# Quick_Mix.net
KiCad netlist of a schematic drawn in EAGLE
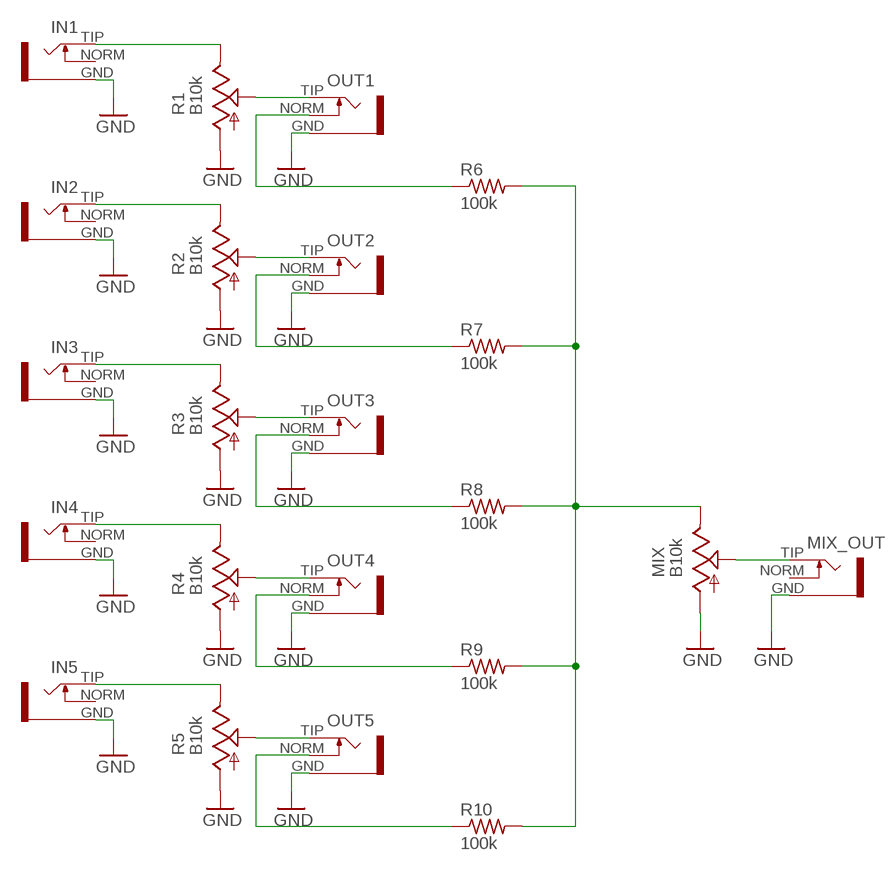
[diagram p0: schematic, sheet 1]

(export (version "E")
  (design (tool "Eeschema 10.0.6"))
  (components
    (comp (ref "IN1")
      (value "INSTRUO_S_JACK_SMALL2")
      (footprint "eagle-import:INSTRUO_S_JACK_SMALL2")
      (libsource (lib "eagle-import") (part "INSTRUO_S_JACK_SMALL2"))
    )
    (comp (ref "IN2")
      (value "INSTRUO_S_JACK_SMALL2")
      (footprint "eagle-import:INSTRUO_S_JACK_SMALL2")
      (libsource (lib "eagle-import") (part "INSTRUO_S_JACK_SMALL2"))
    )
    (comp (ref "IN3")
      (value "INSTRUO_S_JACK_SMALL2")
      (footprint "eagle-import:INSTRUO_S_JACK_SMALL2")
      (libsource (lib "eagle-import") (part "INSTRUO_S_JACK_SMALL2"))
    )
    (comp (ref "IN4")
      (value "INSTRUO_S_JACK_SMALL2")
      (footprint "eagle-import:INSTRUO_S_JACK_SMALL2")
      (libsource (lib "eagle-import") (part "INSTRUO_S_JACK_SMALL2"))
    )
    (comp (ref "IN5")
      (value "INSTRUO_S_JACK_SMALL2")
      (footprint "eagle-import:INSTRUO_S_JACK_SMALL2")
      (libsource (lib "eagle-import") (part "INSTRUO_S_JACK_SMALL2"))
    )
    (comp (ref "MIX")
      (value "B10k")
      (footprint "eagle-import:OG-POTS_ALPS_POT_VERTICAL")
      (libsource (lib "eagle-import") (part "OG-POTS_POT_USVERTICAL"))
    )
    (comp (ref "MIX_OUT")
      (value "INSTRUO_S_JACK_SMALL2")
      (footprint "eagle-import:INSTRUO_S_JACK_SMALL2")
      (libsource (lib "eagle-import") (part "INSTRUO_S_JACK_SMALL2"))
    )
    (comp (ref "OUT1")
      (value "INSTRUO_S_JACK_S2_INV")
      (footprint "eagle-import:INSTRUO_S_JACK_S2_INV")
      (libsource (lib "eagle-import") (part "INSTRUO_S_JACK_S2_INV"))
    )
    (comp (ref "OUT2")
      (value "INSTRUO_S_JACK_S2_INV")
      (footprint "eagle-import:INSTRUO_S_JACK_S2_INV")
      (libsource (lib "eagle-import") (part "INSTRUO_S_JACK_S2_INV"))
    )
    (comp (ref "OUT3")
      (value "INSTRUO_S_JACK_S2_INV")
      (footprint "eagle-import:INSTRUO_S_JACK_S2_INV")
      (libsource (lib "eagle-import") (part "INSTRUO_S_JACK_S2_INV"))
    )
    (comp (ref "OUT4")
      (value "INSTRUO_S_JACK_S2_INV")
      (footprint "eagle-import:INSTRUO_S_JACK_S2_INV")
      (libsource (lib "eagle-import") (part "INSTRUO_S_JACK_S2_INV"))
    )
    (comp (ref "OUT5")
      (value "INSTRUO_S_JACK_S2_INV")
      (footprint "eagle-import:INSTRUO_S_JACK_S2_INV")
      (libsource (lib "eagle-import") (part "INSTRUO_S_JACK_S2_INV"))
    )
    (comp (ref "R1")
      (value "B10k")
      (footprint "eagle-import:OG-POTS_ALPS_POT_VERTICAL")
      (libsource (lib "eagle-import") (part "OG-POTS_POT_USVERTICAL"))
    )
    (comp (ref "R2")
      (value "B10k")
      (footprint "eagle-import:OG-POTS_ALPS_POT_VERTICAL")
      (libsource (lib "eagle-import") (part "OG-POTS_POT_USVERTICAL"))
    )
    (comp (ref "R3")
      (value "B10k")
      (footprint "eagle-import:OG-POTS_ALPS_POT_VERTICAL")
      (libsource (lib "eagle-import") (part "OG-POTS_POT_USVERTICAL"))
    )
    (comp (ref "R4")
      (value "B10k")
      (footprint "eagle-import:OG-POTS_ALPS_POT_VERTICAL")
      (libsource (lib "eagle-import") (part "OG-POTS_POT_USVERTICAL"))
    )
    (comp (ref "R5")
      (value "B10k")
      (footprint "eagle-import:OG-POTS_ALPS_POT_VERTICAL")
      (libsource (lib "eagle-import") (part "OG-POTS_POT_USVERTICAL"))
    )
    (comp (ref "R6")
      (value "100k")
      (footprint "eagle-import:R0603")
      (libsource (lib "eagle-import") (part "R-US_R0603"))
    )
    (comp (ref "R7")
      (value "100k")
      (footprint "eagle-import:R0603")
      (libsource (lib "eagle-import") (part "R-US_R0603"))
    )
    (comp (ref "R8")
      (value "100k")
      (footprint "eagle-import:R0603")
      (libsource (lib "eagle-import") (part "R-US_R0603"))
    )
    (comp (ref "R9")
      (value "100k")
      (footprint "eagle-import:R0603")
      (libsource (lib "eagle-import") (part "R-US_R0603"))
    )
    (comp (ref "R10")
      (value "100k")
      (footprint "eagle-import:R0603")
      (libsource (lib "eagle-import") (part "R-US_R0603"))
    )
  )
  (nets
    (net (code "1") (name "GND") (class "Default")
      (node (ref "IN1") (pin "GND") (pinfunction "GND_GND") (pintype "passive"))
      (node (ref "IN2") (pin "GND") (pinfunction "GND_GND") (pintype "passive"))
      (node (ref "IN3") (pin "GND") (pinfunction "GND_GND") (pintype "passive"))
      (node (ref "IN4") (pin "GND") (pinfunction "GND_GND") (pintype "passive"))
      (node (ref "IN5") (pin "GND") (pinfunction "GND_GND") (pintype "passive"))
      (node (ref "MIX") (pin "P$3") (pinfunction "A_P$3") (pintype "passive"))
      (node (ref "MIX_OUT") (pin "GND") (pinfunction "GND_GND") (pintype "passive"))
      (node (ref "OUT1") (pin "GND") (pinfunction "GND_GND") (pintype "passive"))
      (node (ref "OUT2") (pin "GND") (pinfunction "GND_GND") (pintype "passive"))
      (node (ref "OUT3") (pin "GND") (pinfunction "GND_GND") (pintype "passive"))
      (node (ref "OUT4") (pin "GND") (pinfunction "GND_GND") (pintype "passive"))
      (node (ref "OUT5") (pin "GND") (pinfunction "GND_GND") (pintype "passive"))
      (node (ref "R1") (pin "P$3") (pinfunction "A_P$3") (pintype "passive"))
      (node (ref "R2") (pin "P$3") (pinfunction "A_P$3") (pintype "passive"))
      (node (ref "R3") (pin "P$3") (pinfunction "A_P$3") (pintype "passive"))
      (node (ref "R4") (pin "P$3") (pinfunction "A_P$3") (pintype "passive"))
      (node (ref "R5") (pin "P$3") (pinfunction "A_P$3") (pintype "passive"))
    )
    (net (code "2") (name "Net-(MIX-E)") (class "Default")
      (node (ref "MIX") (pin "P$1") (pinfunction "E_P$1") (pintype "passive"))
      (node (ref "R10") (pin "2") (pinfunction "2_2") (pintype "passive"))
      (node (ref "R6") (pin "2") (pinfunction "2_2") (pintype "passive"))
      (node (ref "R7") (pin "2") (pinfunction "2_2") (pintype "passive"))
      (node (ref "R8") (pin "2") (pinfunction "2_2") (pintype "passive"))
      (node (ref "R9") (pin "2") (pinfunction "2_2") (pintype "passive"))
    )
    (net (code "3") (name "Net-(MIX-S)") (class "Default")
      (node (ref "MIX") (pin "P$2") (pinfunction "S_P$2") (pintype "passive"))
      (node (ref "MIX_OUT") (pin "TIP") (pinfunction "TIP_TIP") (pintype "passive"))
    )
    (net (code "4") (name "Net-(OUT1-PadNORM)") (class "Default")
      (node (ref "OUT1") (pin "NORM") (pinfunction "NORM_NORM") (pintype "passive"))
      (node (ref "R6") (pin "1") (pinfunction "1_1") (pintype "passive"))
    )
    (net (code "5") (name "Net-(OUT2-PadNORM)") (class "Default")
      (node (ref "OUT2") (pin "NORM") (pinfunction "NORM_NORM") (pintype "passive"))
      (node (ref "R7") (pin "1") (pinfunction "1_1") (pintype "passive"))
    )
    (net (code "6") (name "Net-(OUT3-PadNORM)") (class "Default")
      (node (ref "OUT3") (pin "NORM") (pinfunction "NORM_NORM") (pintype "passive"))
      (node (ref "R8") (pin "1") (pinfunction "1_1") (pintype "passive"))
    )
    (net (code "7") (name "Net-(OUT4-PadNORM)") (class "Default")
      (node (ref "OUT4") (pin "NORM") (pinfunction "NORM_NORM") (pintype "passive"))
      (node (ref "R9") (pin "1") (pinfunction "1_1") (pintype "passive"))
    )
    (net (code "8") (name "Net-(OUT5-PadNORM)") (class "Default")
      (node (ref "OUT5") (pin "NORM") (pinfunction "NORM_NORM") (pintype "passive"))
      (node (ref "R10") (pin "1") (pinfunction "1_1") (pintype "passive"))
    )
    (net (code "9") (name "Net-(R1-E)") (class "Default")
      (node (ref "IN1") (pin "TIP") (pinfunction "TIP_TIP") (pintype "passive"))
      (node (ref "R1") (pin "P$1") (pinfunction "E_P$1") (pintype "passive"))
    )
    (net (code "10") (name "Net-(R1-S)") (class "Default")
      (node (ref "OUT1") (pin "TIP") (pinfunction "TIP_TIP") (pintype "passive"))
      (node (ref "R1") (pin "P$2") (pinfunction "S_P$2") (pintype "passive"))
    )
    (net (code "11") (name "Net-(R2-E)") (class "Default")
      (node (ref "IN2") (pin "TIP") (pinfunction "TIP_TIP") (pintype "passive"))
      (node (ref "R2") (pin "P$1") (pinfunction "E_P$1") (pintype "passive"))
    )
    (net (code "12") (name "Net-(R2-S)") (class "Default")
      (node (ref "OUT2") (pin "TIP") (pinfunction "TIP_TIP") (pintype "passive"))
      (node (ref "R2") (pin "P$2") (pinfunction "S_P$2") (pintype "passive"))
    )
    (net (code "13") (name "Net-(R3-E)") (class "Default")
      (node (ref "IN3") (pin "TIP") (pinfunction "TIP_TIP") (pintype "passive"))
      (node (ref "R3") (pin "P$1") (pinfunction "E_P$1") (pintype "passive"))
    )
    (net (code "14") (name "Net-(R3-S)") (class "Default")
      (node (ref "OUT3") (pin "TIP") (pinfunction "TIP_TIP") (pintype "passive"))
      (node (ref "R3") (pin "P$2") (pinfunction "S_P$2") (pintype "passive"))
    )
    (net (code "15") (name "Net-(R4-E)") (class "Default")
      (node (ref "IN4") (pin "TIP") (pinfunction "TIP_TIP") (pintype "passive"))
      (node (ref "R4") (pin "P$1") (pinfunction "E_P$1") (pintype "passive"))
    )
    (net (code "16") (name "Net-(R4-S)") (class "Default")
      (node (ref "OUT4") (pin "TIP") (pinfunction "TIP_TIP") (pintype "passive"))
      (node (ref "R4") (pin "P$2") (pinfunction "S_P$2") (pintype "passive"))
    )
    (net (code "17") (name "Net-(R5-E)") (class "Default")
      (node (ref "IN5") (pin "TIP") (pinfunction "TIP_TIP") (pintype "passive"))
      (node (ref "R5") (pin "P$1") (pinfunction "E_P$1") (pintype "passive"))
    )
    (net (code "18") (name "Net-(R5-S)") (class "Default")
      (node (ref "OUT5") (pin "TIP") (pinfunction "TIP_TIP") (pintype "passive"))
      (node (ref "R5") (pin "P$2") (pinfunction "S_P$2") (pintype "passive"))
    )
    (net (code "19") (name "unconnected-(IN1-PadNORM)") (class "Default")
      (node (ref "IN1") (pin "NORM") (pinfunction "NORM_NORM") (pintype "passive"))
    )
    (net (code "20") (name "unconnected-(IN2-PadNORM)") (class "Default")
      (node (ref "IN2") (pin "NORM") (pinfunction "NORM_NORM") (pintype "passive"))
    )
    (net (code "21") (name "unconnected-(IN3-PadNORM)") (class "Default")
      (node (ref "IN3") (pin "NORM") (pinfunction "NORM_NORM") (pintype "passive"))
    )
    (net (code "22") (name "unconnected-(IN4-PadNORM)") (class "Default")
      (node (ref "IN4") (pin "NORM") (pinfunction "NORM_NORM") (pintype "passive"))
    )
    (net (code "23") (name "unconnected-(IN5-PadNORM)") (class "Default")
      (node (ref "IN5") (pin "NORM") (pinfunction "NORM_NORM") (pintype "passive"))
    )
    (net (code "24") (name "unconnected-(MIX_OUT-PadNORM)") (class "Default")
      (node (ref "MIX_OUT") (pin "NORM") (pinfunction "NORM_NORM") (pintype "passive"))
    )
  )
)
